# audio_spectrum.net
KiCad netlist of a schematic drawn in EAGLE
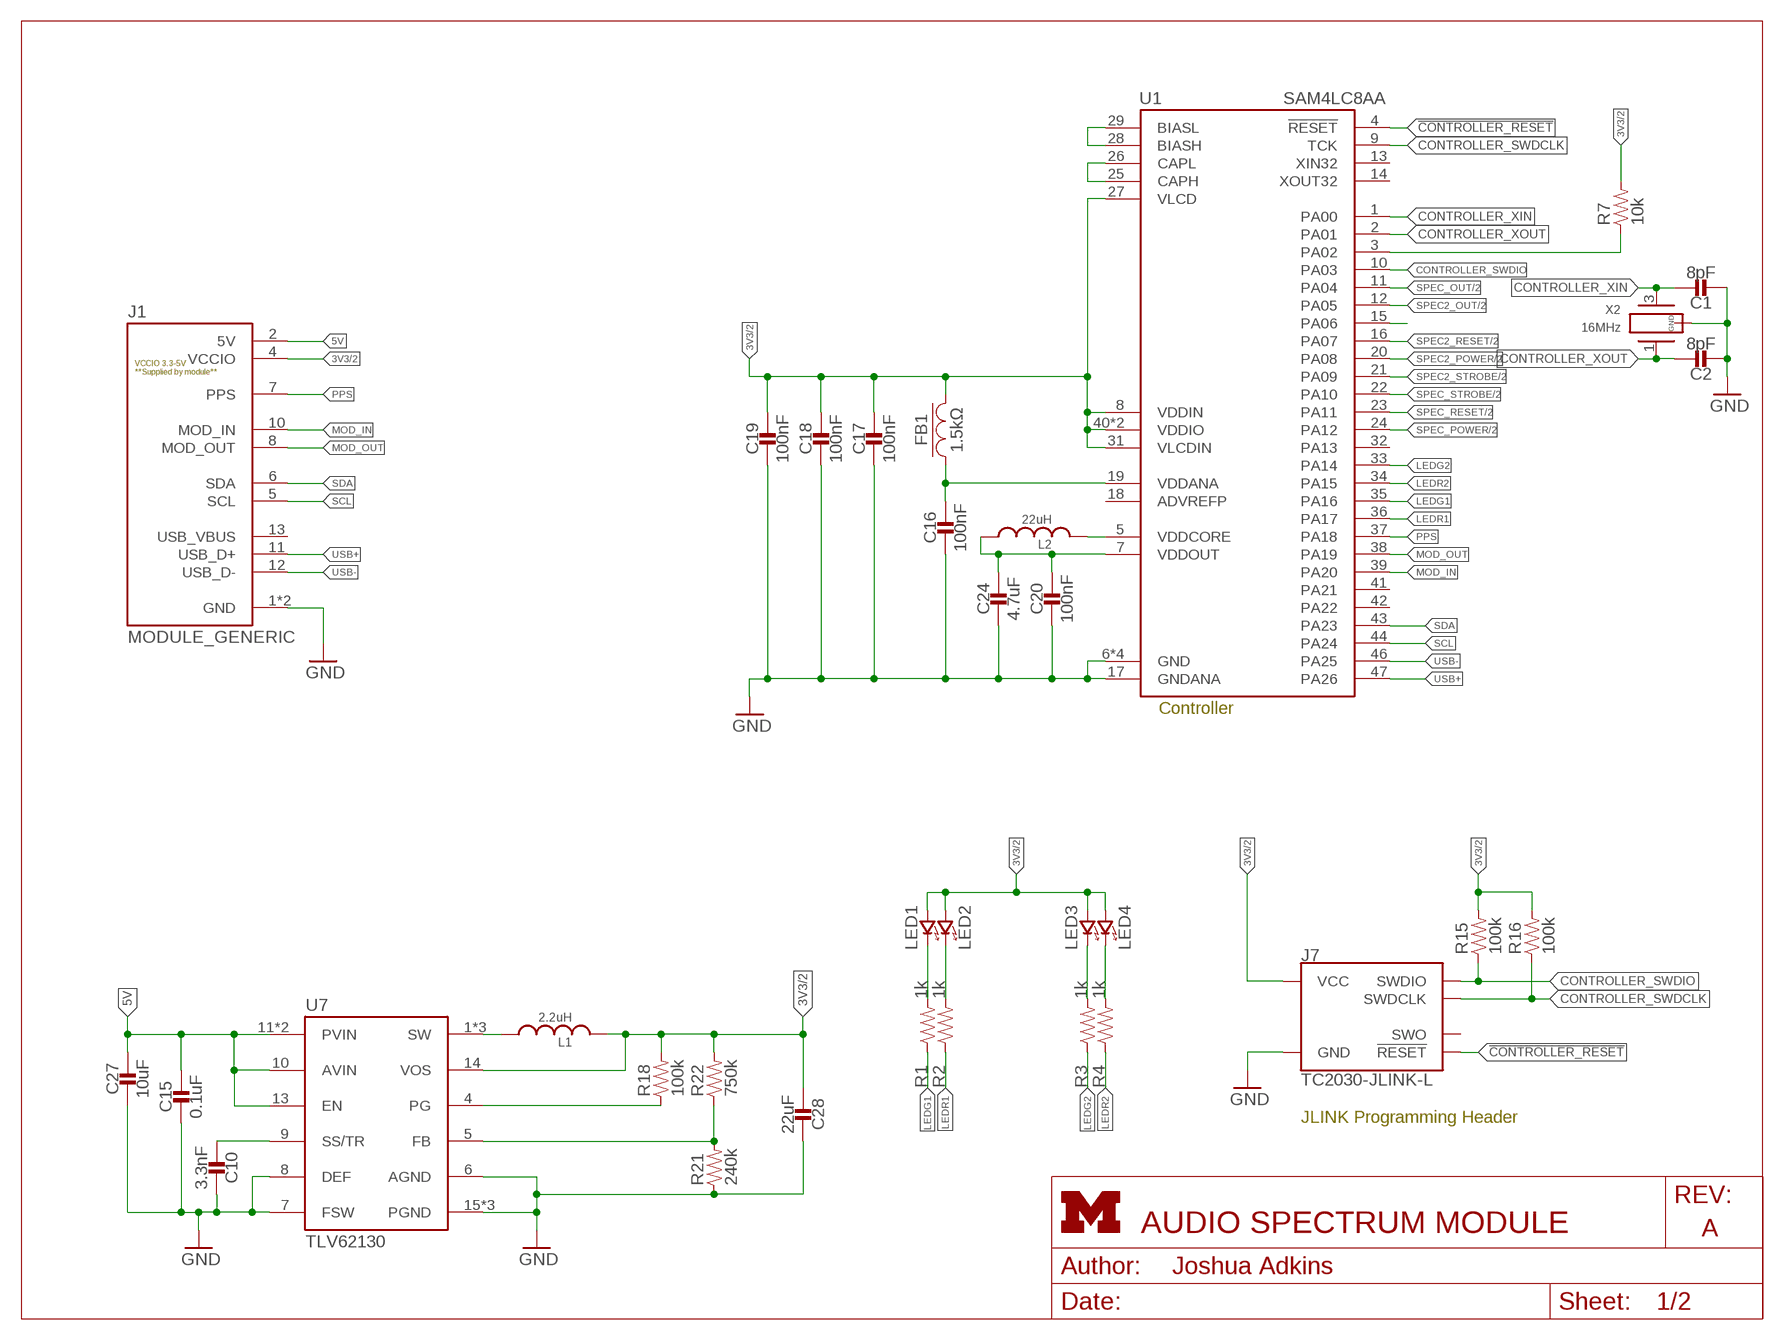
[diagram p0: schematic, sheet 1]
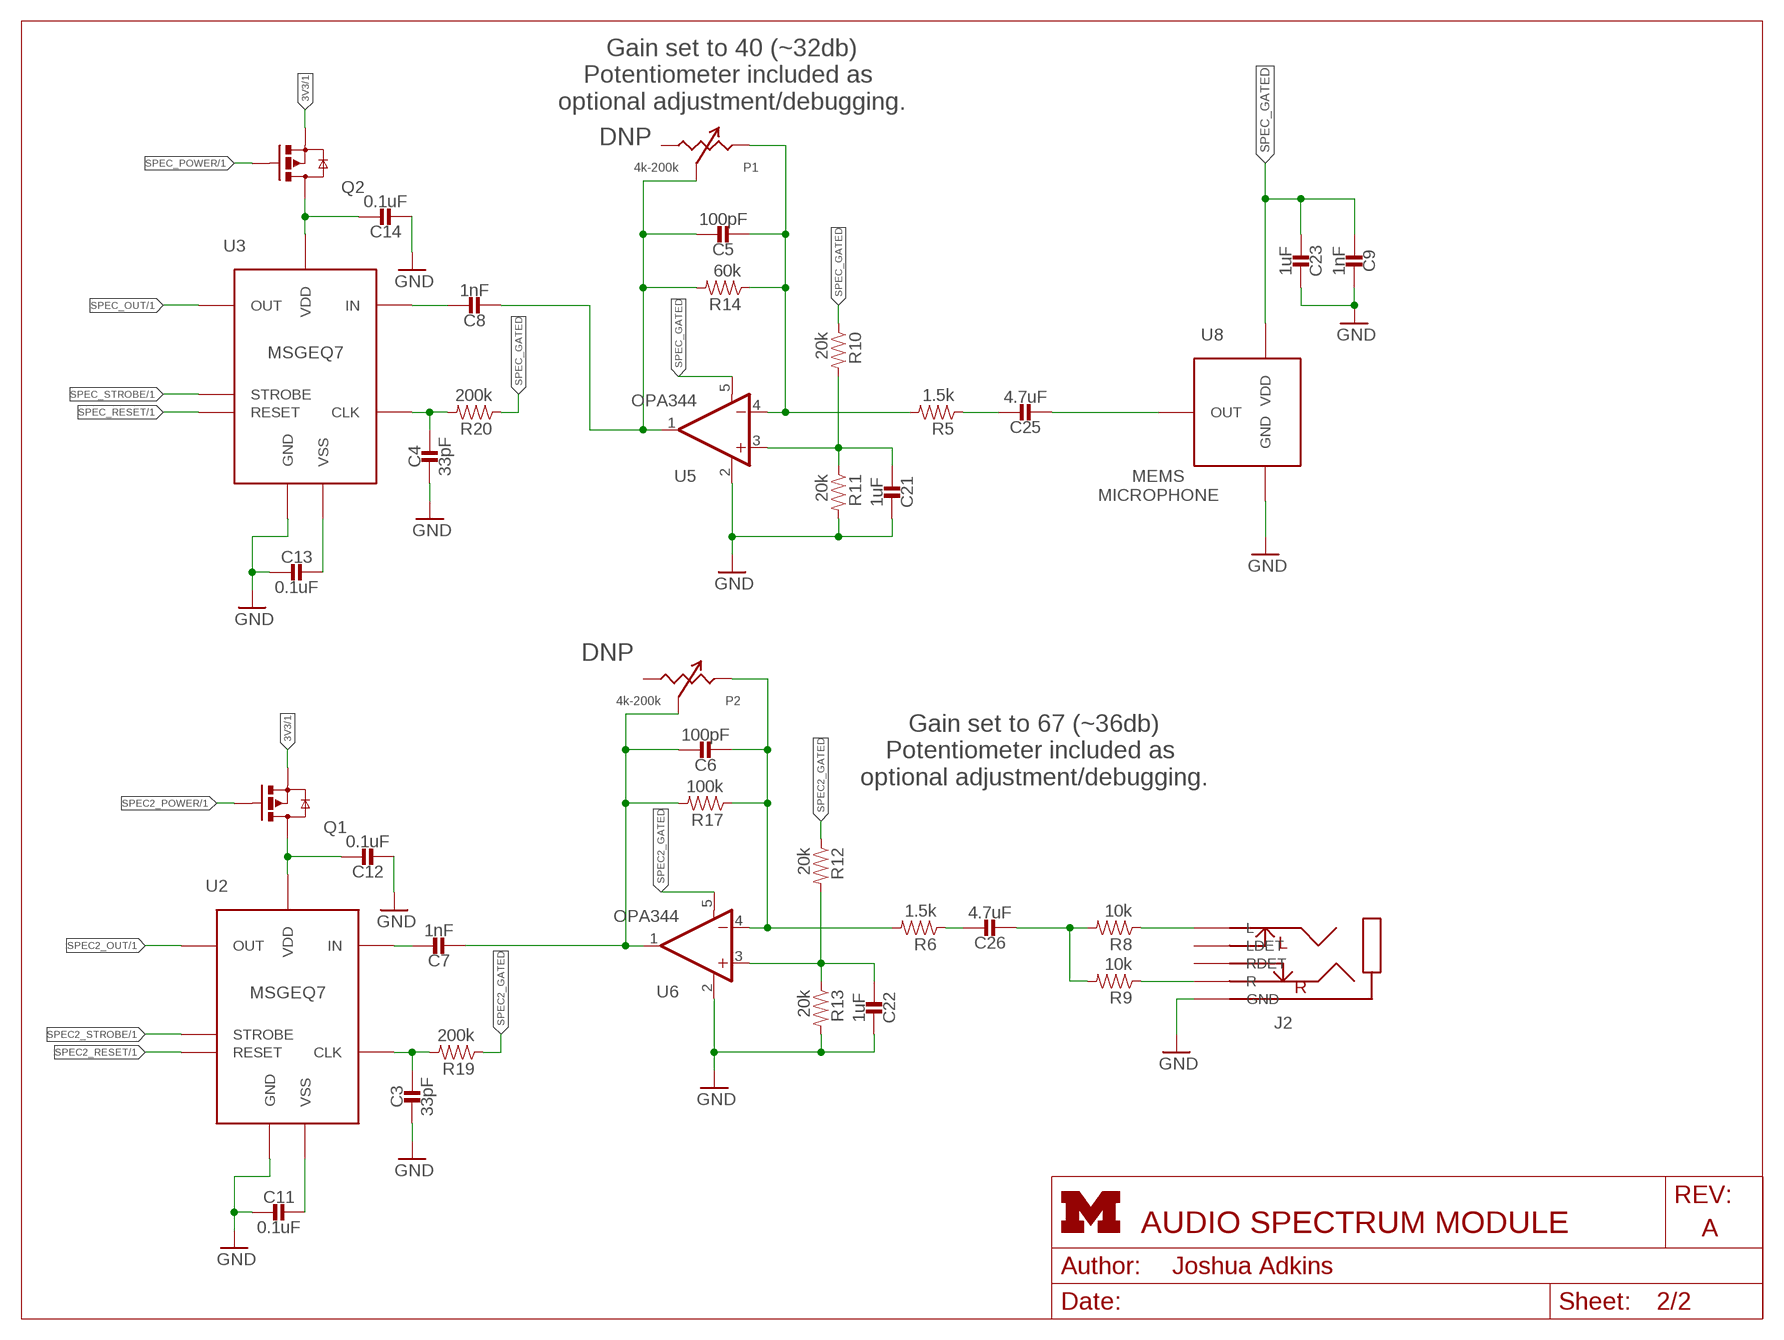
[diagram p1: schematic, sheet 2]

(export (version "E")
  (design (tool "Eeschema 10.0.6"))
  (components
    (comp (ref "C3")
      (value "33pF")
      (footprint "eagle-import:0603_CAP")
      (libsource (lib "eagle-import") (part "CAPACITOR0603_CAP"))
    )
    (comp (ref "C4")
      (value "33pF")
      (footprint "eagle-import:0603_CAP")
      (libsource (lib "eagle-import") (part "CAPACITOR0603_CAP"))
    )
    (comp (ref "C5")
      (value "100pF")
      (footprint "eagle-import:0603_CAP")
      (libsource (lib "eagle-import") (part "CAPACITOR0603_CAP"))
    )
    (comp (ref "C6")
      (value "100pF")
      (footprint "eagle-import:0603_CAP")
      (libsource (lib "eagle-import") (part "CAPACITOR0603_CAP"))
    )
    (comp (ref "C7")
      (value "1nF")
      (footprint "eagle-import:0603_CAP")
      (libsource (lib "eagle-import") (part "CAPACITOR0603_CAP"))
    )
    (comp (ref "C8")
      (value "1nF")
      (footprint "eagle-import:0603_CAP")
      (libsource (lib "eagle-import") (part "CAPACITOR0603_CAP"))
    )
    (comp (ref "C9")
      (value "1nF")
      (footprint "eagle-import:0603_CAP")
      (libsource (lib "eagle-import") (part "CAPACITOR0603_CAP"))
    )
    (comp (ref "C11")
      (value "0.1uF")
      (footprint "eagle-import:0603_CAP")
      (libsource (lib "eagle-import") (part "CAPACITOR0603_CAP"))
    )
    (comp (ref "C12")
      (value "0.1uF")
      (footprint "eagle-import:0603_CAP")
      (libsource (lib "eagle-import") (part "CAPACITOR0603_CAP"))
    )
    (comp (ref "C13")
      (value "0.1uF")
      (footprint "eagle-import:0603_CAP")
      (libsource (lib "eagle-import") (part "CAPACITOR0603_CAP"))
    )
    (comp (ref "C14")
      (value "0.1uF")
      (footprint "eagle-import:0603_CAP")
      (libsource (lib "eagle-import") (part "CAPACITOR0603_CAP"))
    )
    (comp (ref "C21")
      (value "1uF")
      (footprint "eagle-import:0603_CAP")
      (libsource (lib "eagle-import") (part "CAPACITOR0603_CAP"))
    )
    (comp (ref "C22")
      (value "1uF")
      (footprint "eagle-import:0603_CAP")
      (libsource (lib "eagle-import") (part "CAPACITOR0603_CAP"))
    )
    (comp (ref "C23")
      (value "1uF")
      (footprint "eagle-import:0603_CAP")
      (libsource (lib "eagle-import") (part "CAPACITOR0603_CAP"))
    )
    (comp (ref "C25")
      (value "4.7uF")
      (footprint "eagle-import:0603_CAP")
      (libsource (lib "eagle-import") (part "CAPACITOR0603_CAP"))
    )
    (comp (ref "C26")
      (value "4.7uF")
      (footprint "eagle-import:0603_CAP")
      (libsource (lib "eagle-import") (part "CAPACITOR0603_CAP"))
    )
    (comp (ref "J2")
      (value "AUDIO-JACK-VERTICAL")
      (footprint "eagle-import:AUDIO-JACK-VERTICAL")
      (libsource (lib "eagle-import") (part "AUDIO-JACK-VERTICAL"))
    )
    (comp (ref "P1")
      (value "4k-200k")
      (footprint "eagle-import:TC33X-2")
      (libsource (lib "eagle-import") (part "POTTC33X"))
    )
    (comp (ref "P2")
      (value "4k-200k")
      (footprint "eagle-import:TC33X-2")
      (libsource (lib "eagle-import") (part "POTTC33X"))
    )
    (comp (ref "Q1")
      (value "NX3008PBK")
      (footprint "eagle-import:SOT23-3")
      (libsource (lib "eagle-import") (part "NX3008PBK"))
    )
    (comp (ref "Q2")
      (value "NX3008PBK")
      (footprint "eagle-import:SOT23-3")
      (libsource (lib "eagle-import") (part "NX3008PBK"))
    )
    (comp (ref "R5")
      (value "1.5k")
      (footprint "eagle-import:0603-RES")
      (libsource (lib "eagle-import") (part "RESISTOR0603_RES"))
    )
    (comp (ref "R6")
      (value "1.5k")
      (footprint "eagle-import:0603-RES")
      (libsource (lib "eagle-import") (part "RESISTOR0603_RES"))
    )
    (comp (ref "R8")
      (value "10k")
      (footprint "eagle-import:0603-RES")
      (libsource (lib "eagle-import") (part "RESISTOR0603_RES"))
    )
    (comp (ref "R9")
      (value "10k")
      (footprint "eagle-import:0603-RES")
      (libsource (lib "eagle-import") (part "RESISTOR0603_RES"))
    )
    (comp (ref "R10")
      (value "20k")
      (footprint "eagle-import:0603-RES")
      (libsource (lib "eagle-import") (part "RESISTOR0603_RES"))
    )
    (comp (ref "R11")
      (value "20k")
      (footprint "eagle-import:0603-RES")
      (libsource (lib "eagle-import") (part "RESISTOR0603_RES"))
    )
    (comp (ref "R12")
      (value "20k")
      (footprint "eagle-import:0603-RES")
      (libsource (lib "eagle-import") (part "RESISTOR0603_RES"))
    )
    (comp (ref "R13")
      (value "20k")
      (footprint "eagle-import:0603-RES")
      (libsource (lib "eagle-import") (part "RESISTOR0603_RES"))
    )
    (comp (ref "R14")
      (value "60k")
      (footprint "eagle-import:0603-RES")
      (libsource (lib "eagle-import") (part "RESISTOR0603_RES"))
    )
    (comp (ref "R17")
      (value "100k")
      (footprint "eagle-import:0603-RES")
      (libsource (lib "eagle-import") (part "RESISTOR0603_RES"))
    )
    (comp (ref "R19")
      (value "200k")
      (footprint "eagle-import:0603-RES")
      (libsource (lib "eagle-import") (part "RESISTOR0603_RES"))
    )
    (comp (ref "R20")
      (value "200k")
      (footprint "eagle-import:0603-RES")
      (libsource (lib "eagle-import") (part "RESISTOR0603_RES"))
    )
    (comp (ref "U2")
      (value "MSGEQ7")
      (footprint "eagle-import:DIP-8")
      (libsource (lib "eagle-import") (part "MSGEQ7"))
    )
    (comp (ref "U3")
      (value "MSGEQ7")
      (footprint "eagle-import:DIP-8")
      (libsource (lib "eagle-import") (part "MSGEQ7"))
    )
    (comp (ref "U5")
      (value "OPA344")
      (footprint "eagle-import:SOT23-5")
      (libsource (lib "eagle-import") (part "OPA344"))
    )
    (comp (ref "U6")
      (value "OPA344")
      (footprint "eagle-import:SOT23-5")
      (libsource (lib "eagle-import") (part "OPA344"))
    )
    (comp (ref "U8")
      (value "MP23AB02B")
      (footprint "eagle-import:MP23AB02B")
      (libsource (lib "eagle-import") (part "MP23AB02B"))
    )
    (comp (ref "C1")
      (value "8pF")
      (footprint "eagle-import:0603_CAP")
      (libsource (lib "eagle-import") (part "CAPACITOR0603_CAP"))
    )
    (comp (ref "C2")
      (value "8pF")
      (footprint "eagle-import:0603_CAP")
      (libsource (lib "eagle-import") (part "CAPACITOR0603_CAP"))
    )
    (comp (ref "C10")
      (value "3.3nF")
      (footprint "eagle-import:0603_CAP")
      (libsource (lib "eagle-import") (part "CAPACITOR0603_CAP"))
    )
    (comp (ref "C15")
      (value "0.1uF")
      (footprint "eagle-import:0603_CAP")
      (libsource (lib "eagle-import") (part "CAPACITOR0603_CAP"))
    )
    (comp (ref "C16")
      (value "100nF")
      (footprint "eagle-import:0603_CAP")
      (libsource (lib "eagle-import") (part "CAPACITOR0603_CAP"))
    )
    (comp (ref "C17")
      (value "100nF")
      (footprint "eagle-import:0603_CAP")
      (libsource (lib "eagle-import") (part "CAPACITOR0603_CAP"))
    )
    (comp (ref "C18")
      (value "100nF")
      (footprint "eagle-import:0603_CAP")
      (libsource (lib "eagle-import") (part "CAPACITOR0603_CAP"))
    )
    (comp (ref "C19")
      (value "100nF")
      (footprint "eagle-import:0603_CAP")
      (libsource (lib "eagle-import") (part "CAPACITOR0603_CAP"))
    )
    (comp (ref "C20")
      (value "100nF")
      (footprint "eagle-import:0603_CAP")
      (libsource (lib "eagle-import") (part "CAPACITOR0603_CAP"))
    )
    (comp (ref "C24")
      (value "4.7uF")
      (footprint "eagle-import:0603_CAP")
      (libsource (lib "eagle-import") (part "CAPACITOR0603_CAP"))
    )
    (comp (ref "C27")
      (value "10uF")
      (footprint "eagle-import:0603_CAP")
      (libsource (lib "eagle-import") (part "CAPACITOR0603_CAP"))
    )
    (comp (ref "C28")
      (value "22uF")
      (footprint "eagle-import:0603_CAP")
      (libsource (lib "eagle-import") (part "CAPACITOR0603_CAP"))
    )
    (comp (ref "FB1")
      (value "1.5kΩ")
      (footprint "eagle-import:0603_CAP")
      (libsource (lib "eagle-import") (part "FERRITE_BEAD0603"))
    )
    (comp (ref "J1")
      (value "MODULE_GENERIC")
      (footprint "eagle-import:MODULE_GENERIC")
      (libsource (lib "eagle-import") (part "MODULE_GENERIC"))
    )
    (comp (ref "J7")
      (value "TC2030-JLINK-L")
      (footprint "eagle-import:TC2030-IDC")
      (libsource (lib "eagle-import") (part "TC2030-JLINK-L"))
    )
    (comp (ref "L1")
      (value "2.2uH")
      (footprint "eagle-import:IHL-1212BZ-11")
      (libsource (lib "eagle-import") (part "INDUCTORIHL"))
    )
    (comp (ref "L2")
      (value "22uH")
      (footprint "eagle-import:1212")
      (libsource (lib "eagle-import") (part "LHQ3NP"))
    )
    (comp (ref "LED1")
      (value "LED0603")
      (footprint "eagle-import:LED-0603")
      (libsource (lib "eagle-import") (part "LED0603"))
    )
    (comp (ref "LED2")
      (value "LED0603")
      (footprint "eagle-import:LED-0603")
      (libsource (lib "eagle-import") (part "LED0603"))
    )
    (comp (ref "LED3")
      (value "LED0603")
      (footprint "eagle-import:LED-0603")
      (libsource (lib "eagle-import") (part "LED0603"))
    )
    (comp (ref "LED4")
      (value "LED0603")
      (footprint "eagle-import:LED-0603")
      (libsource (lib "eagle-import") (part "LED0603"))
    )
    (comp (ref "R1")
      (value "1k")
      (footprint "eagle-import:0603-RES")
      (libsource (lib "eagle-import") (part "RESISTOR0603_RES"))
    )
    (comp (ref "R2")
      (value "1k")
      (footprint "eagle-import:0603-RES")
      (libsource (lib "eagle-import") (part "RESISTOR0603_RES"))
    )
    (comp (ref "R3")
      (value "1k")
      (footprint "eagle-import:0603-RES")
      (libsource (lib "eagle-import") (part "RESISTOR0603_RES"))
    )
    (comp (ref "R4")
      (value "1k")
      (footprint "eagle-import:0603-RES")
      (libsource (lib "eagle-import") (part "RESISTOR0603_RES"))
    )
    (comp (ref "R7")
      (value "10k")
      (footprint "eagle-import:0603-RES")
      (libsource (lib "eagle-import") (part "RESISTOR0603_RES"))
    )
    (comp (ref "R15")
      (value "100k")
      (footprint "eagle-import:0603-RES")
      (libsource (lib "eagle-import") (part "RESISTOR0603_RES"))
    )
    (comp (ref "R16")
      (value "100k")
      (footprint "eagle-import:0603-RES")
      (libsource (lib "eagle-import") (part "RESISTOR0603_RES"))
    )
    (comp (ref "R18")
      (value "100k")
      (footprint "eagle-import:0603-RES")
      (libsource (lib "eagle-import") (part "RESISTOR0603_RES"))
    )
    (comp (ref "R21")
      (value "240k")
      (footprint "eagle-import:0603-RES")
      (libsource (lib "eagle-import") (part "RESISTOR0603_RES"))
    )
    (comp (ref "R22")
      (value "750k")
      (footprint "eagle-import:0603-RES")
      (libsource (lib "eagle-import") (part "RESISTOR0603_RES"))
    )
    (comp (ref "U1")
      (value "SAM4LC8AA")
      (footprint "eagle-import:QFN-48-7MM")
      (libsource (lib "eagle-import") (part "SAM4LC8AA"))
    )
    (comp (ref "U7")
      (value "TLV62130")
      (footprint "eagle-import:TQFN-16_3MM")
      (libsource (lib "eagle-import") (part "TLV62130"))
    )
    (comp (ref "X2")
      (value "16MHz")
      (footprint "eagle-import:FHXXX")
      (libsource (lib "eagle-import") (part "FH1600015"))
    )
  )
  (nets
    (net (code "1") (name "3V3") (class "Default")
      (node (ref "C17") (pin "1") (pinfunction "1_1") (pintype "bidirectional"))
      (node (ref "C18") (pin "1") (pinfunction "1_1") (pintype "bidirectional"))
      (node (ref "C19") (pin "1") (pinfunction "1_1") (pintype "bidirectional"))
      (node (ref "C28") (pin "2") (pinfunction "2_2") (pintype "bidirectional"))
      (node (ref "FB1") (pin "2") (pinfunction "P$2_2") (pintype "bidirectional"))
      (node (ref "J1") (pin "4") (pinfunction "VCCIO_4") (pintype "bidirectional"))
      (node (ref "J7") (pin "1") (pinfunction "VCC_1") (pintype "bidirectional"))
      (node (ref "L1") (pin "P$2") (pinfunction "2_P$2") (pintype "bidirectional"))
      (node (ref "LED1") (pin "A") (pinfunction "ANODE_A") (pintype "bidirectional"))
      (node (ref "LED2") (pin "A") (pinfunction "ANODE_A") (pintype "bidirectional"))
      (node (ref "LED3") (pin "A") (pinfunction "ANODE_A") (pintype "bidirectional"))
      (node (ref "LED4") (pin "A") (pinfunction "ANODE_A") (pintype "bidirectional"))
      (node (ref "Q1") (pin "2") (pinfunction "S_2") (pintype "passive"))
      (node (ref "Q2") (pin "2") (pinfunction "S_2") (pintype "passive"))
      (node (ref "R15") (pin "2") (pinfunction "2_2") (pintype "passive"))
      (node (ref "R16") (pin "2") (pinfunction "2_2") (pintype "passive"))
      (node (ref "R18") (pin "2") (pinfunction "2_2") (pintype "passive"))
      (node (ref "R22") (pin "2") (pinfunction "2_2") (pintype "passive"))
      (node (ref "R7") (pin "2") (pinfunction "2_2") (pintype "passive"))
      (node (ref "U1") (pin "27") (pinfunction "VLCD_27") (pintype "bidirectional"))
      (node (ref "U1") (pin "31") (pinfunction "VLCDIN_31") (pintype "power_in"))
      (node (ref "U1") (pin "40") (pinfunction "VDDIO_40") (pintype "power_in"))
      (node (ref "U1") (pin "45") (pinfunction "VDDIO_45") (pintype "power_in"))
      (node (ref "U1") (pin "8") (pinfunction "VDDIN_8") (pintype "power_in"))
      (node (ref "U7") (pin "14") (pinfunction "VOS_14") (pintype "bidirectional"))
    )
    (net (code "2") (name "5V") (class "Default")
      (node (ref "C15") (pin "1") (pinfunction "1_1") (pintype "bidirectional"))
      (node (ref "C27") (pin "1") (pinfunction "1_1") (pintype "bidirectional"))
      (node (ref "J1") (pin "2") (pinfunction "5V_2") (pintype "bidirectional"))
      (node (ref "U7") (pin "10") (pinfunction "AVIN_10") (pintype "bidirectional"))
      (node (ref "U7") (pin "11") (pinfunction "PVIN_11") (pintype "bidirectional"))
      (node (ref "U7") (pin "12") (pinfunction "PVIN_12") (pintype "bidirectional"))
      (node (ref "U7") (pin "13") (pinfunction "EN_13") (pintype "bidirectional"))
    )
    (net (code "3") (name "CONTROLLER_SWDCLK") (class "Default")
      (node (ref "J7") (pin "4") (pinfunction "SWDCLK_4") (pintype "bidirectional"))
      (node (ref "R16") (pin "1") (pinfunction "1_1") (pintype "passive"))
      (node (ref "U1") (pin "9") (pinfunction "TCK_9") (pintype "bidirectional"))
    )
    (net (code "4") (name "CONTROLLER_SWDIO") (class "Default")
      (node (ref "J7") (pin "2") (pinfunction "SWDIO_2") (pintype "bidirectional"))
      (node (ref "R15") (pin "1") (pinfunction "1_1") (pintype "passive"))
      (node (ref "U1") (pin "10") (pinfunction "PA03_10") (pintype "bidirectional"))
    )
    (net (code "5") (name "CONTROLLER_XIN") (class "Default")
      (node (ref "C1") (pin "1") (pinfunction "1_1") (pintype "bidirectional"))
      (node (ref "U1") (pin "1") (pinfunction "PA00_1") (pintype "bidirectional"))
      (node (ref "X2") (pin "3") (pinfunction "2_3") (pintype "bidirectional"))
    )
    (net (code "6") (name "CONTROLLER_XOUT") (class "Default")
      (node (ref "C2") (pin "1") (pinfunction "1_1") (pintype "bidirectional"))
      (node (ref "U1") (pin "2") (pinfunction "PA01_2") (pintype "bidirectional"))
      (node (ref "X2") (pin "1") (pinfunction "1_1") (pintype "bidirectional"))
    )
    (net (code "7") (name "GND") (class "Default")
      (node (ref "C1") (pin "2") (pinfunction "2_2") (pintype "bidirectional"))
      (node (ref "C10") (pin "1") (pinfunction "1_1") (pintype "bidirectional"))
      (node (ref "C11") (pin "2") (pinfunction "2_2") (pintype "bidirectional"))
      (node (ref "C12") (pin "2") (pinfunction "2_2") (pintype "bidirectional"))
      (node (ref "C13") (pin "2") (pinfunction "2_2") (pintype "bidirectional"))
      (node (ref "C14") (pin "2") (pinfunction "2_2") (pintype "bidirectional"))
      (node (ref "C15") (pin "2") (pinfunction "2_2") (pintype "bidirectional"))
      (node (ref "C16") (pin "2") (pinfunction "2_2") (pintype "bidirectional"))
      (node (ref "C17") (pin "2") (pinfunction "2_2") (pintype "bidirectional"))
      (node (ref "C18") (pin "2") (pinfunction "2_2") (pintype "bidirectional"))
      (node (ref "C19") (pin "2") (pinfunction "2_2") (pintype "bidirectional"))
      (node (ref "C2") (pin "2") (pinfunction "2_2") (pintype "bidirectional"))
      (node (ref "C20") (pin "2") (pinfunction "2_2") (pintype "bidirectional"))
      (node (ref "C21") (pin "1") (pinfunction "1_1") (pintype "bidirectional"))
      (node (ref "C22") (pin "1") (pinfunction "1_1") (pintype "bidirectional"))
      (node (ref "C23") (pin "1") (pinfunction "1_1") (pintype "bidirectional"))
      (node (ref "C24") (pin "2") (pinfunction "2_2") (pintype "bidirectional"))
      (node (ref "C27") (pin "2") (pinfunction "2_2") (pintype "bidirectional"))
      (node (ref "C28") (pin "1") (pinfunction "1_1") (pintype "bidirectional"))
      (node (ref "C3") (pin "2") (pinfunction "2_2") (pintype "bidirectional"))
      (node (ref "C4") (pin "2") (pinfunction "2_2") (pintype "bidirectional"))
      (node (ref "C9") (pin "1") (pinfunction "1_1") (pintype "bidirectional"))
      (node (ref "J1") (pin "1") (pinfunction "GND_1") (pintype "bidirectional"))
      (node (ref "J1") (pin "14") (pinfunction "GND_14") (pintype "bidirectional"))
      (node (ref "J2") (pin "5") (pinfunction "GND_5") (pintype "bidirectional"))
      (node (ref "J7") (pin "5") (pinfunction "GND_5") (pintype "bidirectional"))
      (node (ref "R11") (pin "2") (pinfunction "2_2") (pintype "passive"))
      (node (ref "R13") (pin "2") (pinfunction "2_2") (pintype "passive"))
      (node (ref "R21") (pin "1") (pinfunction "1_1") (pintype "passive"))
      (node (ref "U1") (pin "17") (pinfunction "GNDANA_17") (pintype "power_in"))
      (node (ref "U1") (pin "30") (pinfunction "GND_30") (pintype "power_in"))
      (node (ref "U1") (pin "48") (pinfunction "GND_48") (pintype "power_in"))
      (node (ref "U1") (pin "6") (pinfunction "GND_6") (pintype "power_in"))
      (node (ref "U1") (pin "THERMAL") (pinfunction "GND_THERMAL") (pintype "power_in"))
      (node (ref "U2") (pin "6") (pinfunction "GND_6") (pintype "bidirectional"))
      (node (ref "U3") (pin "6") (pinfunction "GND_6") (pintype "bidirectional"))
      (node (ref "U5") (pin "2") (pinfunction "V-_2") (pintype "power_in"))
      (node (ref "U6") (pin "2") (pinfunction "V-_2") (pintype "power_in"))
      (node (ref "U7") (pin "15") (pinfunction "PGND_15") (pintype "bidirectional"))
      (node (ref "U7") (pin "16") (pinfunction "PGND_16") (pintype "bidirectional"))
      (node (ref "U7") (pin "6") (pinfunction "AGND_6") (pintype "bidirectional"))
      (node (ref "U7") (pin "7") (pinfunction "FSW_7") (pintype "bidirectional"))
      (node (ref "U7") (pin "8") (pinfunction "DEF_8") (pintype "bidirectional"))
      (node (ref "U7") (pin "GND") (pinfunction "PGND_GND") (pintype "bidirectional"))
      (node (ref "U8") (pin "3") (pinfunction "GND_3") (pintype "bidirectional"))
      (node (ref "X2") (pin "2") (pinfunction "GND_2") (pintype "bidirectional"))
      (node (ref "X2") (pin "4") (pinfunction "GND_4") (pintype "bidirectional"))
    )
    (net (code "8") (name "LEDG1") (class "Default")
      (node (ref "R1") (pin "1") (pinfunction "1_1") (pintype "passive"))
      (node (ref "U1") (pin "35") (pinfunction "PA16_35") (pintype "bidirectional"))
    )
    (net (code "9") (name "LEDG2") (class "Default")
      (node (ref "R3") (pin "1") (pinfunction "1_1") (pintype "passive"))
      (node (ref "U1") (pin "33") (pinfunction "PA14_33") (pintype "bidirectional"))
    )
    (net (code "10") (name "LEDR1") (class "Default")
      (node (ref "R2") (pin "1") (pinfunction "1_1") (pintype "passive"))
      (node (ref "U1") (pin "36") (pinfunction "PA17_36") (pintype "bidirectional"))
    )
    (net (code "11") (name "LEDR2") (class "Default")
      (node (ref "R4") (pin "1") (pinfunction "1_1") (pintype "passive"))
      (node (ref "U1") (pin "34") (pinfunction "PA15_34") (pintype "bidirectional"))
    )
    (net (code "12") (name "MOD_IN") (class "Default")
      (node (ref "J1") (pin "10") (pinfunction "MOD_IN_10") (pintype "bidirectional"))
      (node (ref "U1") (pin "39") (pinfunction "PA20_39") (pintype "bidirectional"))
    )
    (net (code "13") (name "MOD_OUT") (class "Default")
      (node (ref "J1") (pin "8") (pinfunction "MOD_OUT_8") (pintype "bidirectional"))
      (node (ref "U1") (pin "38") (pinfunction "PA19_38") (pintype "bidirectional"))
    )
    (net (code "14") (name "Net-(C25-Pad1)") (class "Default")
      (node (ref "C25") (pin "1") (pinfunction "1_1") (pintype "bidirectional"))
      (node (ref "R5") (pin "1") (pinfunction "1_1") (pintype "passive"))
    )
    (net (code "15") (name "Net-(C26-Pad1)") (class "Default")
      (node (ref "C26") (pin "1") (pinfunction "1_1") (pintype "bidirectional"))
      (node (ref "R6") (pin "1") (pinfunction "1_1") (pintype "passive"))
    )
    (net (code "16") (name "Net-(C26-Pad2)") (class "Default")
      (node (ref "C26") (pin "2") (pinfunction "2_2") (pintype "bidirectional"))
      (node (ref "R8") (pin "2") (pinfunction "2_2") (pintype "passive"))
      (node (ref "R9") (pin "2") (pinfunction "2_2") (pintype "passive"))
    )
    (net (code "17") (name "Net-(FB1-P$1)") (class "Default")
      (node (ref "C16") (pin "1") (pinfunction "1_1") (pintype "bidirectional"))
      (node (ref "FB1") (pin "1") (pinfunction "P$1_1") (pintype "bidirectional"))
      (node (ref "U1") (pin "19") (pinfunction "VDDANA_19") (pintype "power_in"))
    )
    (net (code "18") (name "Net-(J2-L)") (class "Default")
      (node (ref "J2") (pin "4") (pinfunction "L_4") (pintype "bidirectional"))
      (node (ref "R8") (pin "1") (pinfunction "1_1") (pintype "passive"))
    )
    (net (code "19") (name "Net-(J2-R)") (class "Default")
      (node (ref "J2") (pin "1") (pinfunction "R_1") (pintype "bidirectional"))
      (node (ref "R9") (pin "1") (pinfunction "1_1") (pintype "passive"))
    )
    (net (code "20") (name "Net-(L1-1)") (class "Default")
      (node (ref "L1") (pin "P$1") (pinfunction "1_P$1") (pintype "bidirectional"))
      (node (ref "U7") (pin "1") (pinfunction "SW_1") (pintype "bidirectional"))
      (node (ref "U7") (pin "2") (pinfunction "SW_2") (pintype "bidirectional"))
      (node (ref "U7") (pin "3") (pinfunction "SW_3") (pintype "bidirectional"))
    )
    (net (code "21") (name "Net-(L2-1)") (class "Default")
      (node (ref "C20") (pin "1") (pinfunction "1_1") (pintype "bidirectional"))
      (node (ref "C24") (pin "1") (pinfunction "1_1") (pintype "bidirectional"))
      (node (ref "L2") (pin "P$1") (pinfunction "1_P$1") (pintype "bidirectional"))
      (node (ref "U1") (pin "7") (pinfunction "VDDOUT_7") (pintype "power_in"))
    )
    (net (code "22") (name "Net-(L2-2)") (class "Default")
      (node (ref "L2") (pin "P$2") (pinfunction "2_P$2") (pintype "bidirectional"))
      (node (ref "U1") (pin "5") (pinfunction "VDDCORE_5") (pintype "power_in"))
    )
    (net (code "23") (name "Net-(LED1-CATHODE)") (class "Default")
      (node (ref "LED1") (pin "C") (pinfunction "CATHODE_C") (pintype "bidirectional"))
      (node (ref "R1") (pin "2") (pinfunction "2_2") (pintype "passive"))
    )
    (net (code "24") (name "Net-(LED2-CATHODE)") (class "Default")
      (node (ref "LED2") (pin "C") (pinfunction "CATHODE_C") (pintype "bidirectional"))
      (node (ref "R2") (pin "2") (pinfunction "2_2") (pintype "passive"))
    )
    (net (code "25") (name "Net-(LED3-CATHODE)") (class "Default")
      (node (ref "LED3") (pin "C") (pinfunction "CATHODE_C") (pintype "bidirectional"))
      (node (ref "R3") (pin "2") (pinfunction "2_2") (pintype "passive"))
    )
    (net (code "26") (name "Net-(LED4-CATHODE)") (class "Default")
      (node (ref "LED4") (pin "C") (pinfunction "CATHODE_C") (pintype "bidirectional"))
      (node (ref "R4") (pin "2") (pinfunction "2_2") (pintype "passive"))
    )
    (net (code "27") (name "Net-(P1-CW)") (class "Default")
      (node (ref "C5") (pin "2") (pinfunction "2_2") (pintype "bidirectional"))
      (node (ref "P1") (pin "2") (pinfunction "CW_2") (pintype "bidirectional"))
      (node (ref "R14") (pin "1") (pinfunction "1_1") (pintype "passive"))
      (node (ref "R5") (pin "2") (pinfunction "2_2") (pintype "passive"))
      (node (ref "U5") (pin "4") (pinfunction "-IN_4") (pintype "input"))
    )
    (net (code "28") (name "Net-(P1-W)") (class "Default")
      (node (ref "C5") (pin "1") (pinfunction "1_1") (pintype "bidirectional"))
      (node (ref "C8") (pin "2") (pinfunction "2_2") (pintype "bidirectional"))
      (node (ref "P1") (pin "3") (pinfunction "W_3") (pintype "bidirectional"))
      (node (ref "R14") (pin "2") (pinfunction "2_2") (pintype "passive"))
      (node (ref "U5") (pin "1") (pinfunction "OUT_1") (pintype "output"))
    )
    (net (code "29") (name "Net-(P2-CW)") (class "Default")
      (node (ref "C6") (pin "2") (pinfunction "2_2") (pintype "bidirectional"))
      (node (ref "P2") (pin "2") (pinfunction "CW_2") (pintype "bidirectional"))
      (node (ref "R17") (pin "1") (pinfunction "1_1") (pintype "passive"))
      (node (ref "R6") (pin "2") (pinfunction "2_2") (pintype "passive"))
      (node (ref "U6") (pin "4") (pinfunction "-IN_4") (pintype "input"))
    )
    (net (code "30") (name "Net-(P2-W)") (class "Default")
      (node (ref "C6") (pin "1") (pinfunction "1_1") (pintype "bidirectional"))
      (node (ref "C7") (pin "2") (pinfunction "2_2") (pintype "bidirectional"))
      (node (ref "P2") (pin "3") (pinfunction "W_3") (pintype "bidirectional"))
      (node (ref "R17") (pin "2") (pinfunction "2_2") (pintype "passive"))
      (node (ref "U6") (pin "1") (pinfunction "OUT_1") (pintype "output"))
    )
    (net (code "31") (name "Net-(U1-BIASH)") (class "Default")
      (node (ref "U1") (pin "28") (pinfunction "BIASH_28") (pintype "bidirectional"))
      (node (ref "U1") (pin "29") (pinfunction "BIASL_29") (pintype "bidirectional"))
    )
    (net (code "32") (name "Net-(U1-CAPH)") (class "Default")
      (node (ref "U1") (pin "25") (pinfunction "CAPH_25") (pintype "bidirectional"))
      (node (ref "U1") (pin "26") (pinfunction "CAPL_26") (pintype "bidirectional"))
    )
    (net (code "33") (name "Net-(U1-PA02)") (class "Default")
      (node (ref "R7") (pin "1") (pinfunction "1_1") (pintype "passive"))
      (node (ref "U1") (pin "3") (pinfunction "PA02_3") (pintype "bidirectional"))
    )
    (net (code "34") (name "Net-(U2-CLK)") (class "Default")
      (node (ref "C3") (pin "1") (pinfunction "1_1") (pintype "bidirectional"))
      (node (ref "R19") (pin "2") (pinfunction "2_2") (pintype "passive"))
      (node (ref "U2") (pin "8") (pinfunction "CLK_8") (pintype "bidirectional"))
    )
    (net (code "35") (name "Net-(U2-IN)") (class "Default")
      (node (ref "C7") (pin "1") (pinfunction "1_1") (pintype "bidirectional"))
      (node (ref "U2") (pin "5") (pinfunction "IN_5") (pintype "bidirectional"))
    )
    (net (code "36") (name "Net-(U2-VSS)") (class "Default")
      (node (ref "C11") (pin "1") (pinfunction "1_1") (pintype "bidirectional"))
      (node (ref "U2") (pin "2") (pinfunction "VSS_2") (pintype "bidirectional"))
    )
    (net (code "37") (name "Net-(U3-CLK)") (class "Default")
      (node (ref "C4") (pin "1") (pinfunction "1_1") (pintype "bidirectional"))
      (node (ref "R20") (pin "2") (pinfunction "2_2") (pintype "passive"))
      (node (ref "U3") (pin "8") (pinfunction "CLK_8") (pintype "bidirectional"))
    )
    (net (code "38") (name "Net-(U3-IN)") (class "Default")
      (node (ref "C8") (pin "1") (pinfunction "1_1") (pintype "bidirectional"))
      (node (ref "U3") (pin "5") (pinfunction "IN_5") (pintype "bidirectional"))
    )
    (net (code "39") (name "Net-(U3-VSS)") (class "Default")
      (node (ref "C13") (pin "1") (pinfunction "1_1") (pintype "bidirectional"))
      (node (ref "U3") (pin "2") (pinfunction "VSS_2") (pintype "bidirectional"))
    )
    (net (code "40") (name "Net-(U5-+IN)") (class "Default")
      (node (ref "C21") (pin "2") (pinfunction "2_2") (pintype "bidirectional"))
      (node (ref "R10") (pin "2") (pinfunction "2_2") (pintype "passive"))
      (node (ref "R11") (pin "1") (pinfunction "1_1") (pintype "passive"))
      (node (ref "U5") (pin "3") (pinfunction "+IN_3") (pintype "input"))
    )
    (net (code "41") (name "Net-(U6-+IN)") (class "Default")
      (node (ref "C22") (pin "2") (pinfunction "2_2") (pintype "bidirectional"))
      (node (ref "R12") (pin "2") (pinfunction "2_2") (pintype "passive"))
      (node (ref "R13") (pin "1") (pinfunction "1_1") (pintype "passive"))
      (node (ref "U6") (pin "3") (pinfunction "+IN_3") (pintype "input"))
    )
    (net (code "42") (name "Net-(U7-FB)") (class "Default")
      (node (ref "R21") (pin "2") (pinfunction "2_2") (pintype "passive"))
      (node (ref "R22") (pin "1") (pinfunction "1_1") (pintype "passive"))
      (node (ref "U7") (pin "5") (pinfunction "FB_5") (pintype "bidirectional"))
    )
    (net (code "43") (name "Net-(U7-PG)") (class "Default")
      (node (ref "R18") (pin "1") (pinfunction "1_1") (pintype "passive"))
      (node (ref "U7") (pin "4") (pinfunction "PG_4") (pintype "bidirectional"))
    )
    (net (code "44") (name "Net-(U7-SS{slash}TR)") (class "Default")
      (node (ref "C10") (pin "2") (pinfunction "2_2") (pintype "bidirectional"))
      (node (ref "U7") (pin "9") (pinfunction "SS/TR_9") (pintype "bidirectional"))
    )
    (net (code "45") (name "Net-(U8-OUT)") (class "Default")
      (node (ref "C25") (pin "2") (pinfunction "2_2") (pintype "bidirectional"))
      (node (ref "U8") (pin "1") (pinfunction "OUT_1") (pintype "bidirectional"))
    )
    (net (code "46") (name "PPS") (class "Default")
      (node (ref "J1") (pin "7") (pinfunction "PPS_7") (pintype "bidirectional"))
      (node (ref "U1") (pin "37") (pinfunction "PA18_37") (pintype "bidirectional"))
    )
    (net (code "47") (name "SCL") (class "Default")
      (node (ref "J1") (pin "5") (pinfunction "SCL_5") (pintype "bidirectional"))
      (node (ref "U1") (pin "44") (pinfunction "PA24_44") (pintype "bidirectional"))
    )
    (net (code "48") (name "SDA") (class "Default")
      (node (ref "J1") (pin "6") (pinfunction "SDA_6") (pintype "bidirectional"))
      (node (ref "U1") (pin "43") (pinfunction "PA23_43") (pintype "bidirectional"))
    )
    (net (code "49") (name "SPEC2_GATED") (class "Default")
      (node (ref "C12") (pin "1") (pinfunction "1_1") (pintype "bidirectional"))
      (node (ref "Q1") (pin "3") (pinfunction "D_3") (pintype "passive"))
      (node (ref "R12") (pin "1") (pinfunction "1_1") (pintype "passive"))
      (node (ref "R19") (pin "1") (pinfunction "1_1") (pintype "passive"))
      (node (ref "U2") (pin "1") (pinfunction "VDD_1") (pintype "bidirectional"))
      (node (ref "U6") (pin "5") (pinfunction "V+_5") (pintype "power_in"))
    )
    (net (code "50") (name "SPEC2_OUT") (class "Default")
      (node (ref "U1") (pin "12") (pinfunction "PA05_12") (pintype "bidirectional"))
      (node (ref "U2") (pin "3") (pinfunction "OUT_3") (pintype "bidirectional"))
    )
    (net (code "51") (name "SPEC2_POWER") (class "Default")
      (node (ref "Q1") (pin "1") (pinfunction "G_1") (pintype "passive"))
      (node (ref "U1") (pin "20") (pinfunction "PA08_20") (pintype "bidirectional"))
    )
    (net (code "52") (name "SPEC2_RESET") (class "Default")
      (node (ref "U1") (pin "16") (pinfunction "PA07_16") (pintype "bidirectional"))
      (node (ref "U2") (pin "7") (pinfunction "RESET_7") (pintype "bidirectional"))
    )
    (net (code "53") (name "SPEC2_STROBE") (class "Default")
      (node (ref "U1") (pin "21") (pinfunction "PA09_21") (pintype "bidirectional"))
      (node (ref "U2") (pin "4") (pinfunction "STROBE_4") (pintype "bidirectional"))
    )
    (net (code "54") (name "SPEC_GATED") (class "Default")
      (node (ref "C14") (pin "1") (pinfunction "1_1") (pintype "bidirectional"))
      (node (ref "C23") (pin "2") (pinfunction "2_2") (pintype "bidirectional"))
      (node (ref "C9") (pin "2") (pinfunction "2_2") (pintype "bidirectional"))
      (node (ref "Q2") (pin "3") (pinfunction "D_3") (pintype "passive"))
      (node (ref "R10") (pin "1") (pinfunction "1_1") (pintype "passive"))
      (node (ref "R20") (pin "1") (pinfunction "1_1") (pintype "passive"))
      (node (ref "U3") (pin "1") (pinfunction "VDD_1") (pintype "bidirectional"))
      (node (ref "U5") (pin "5") (pinfunction "V+_5") (pintype "power_in"))
      (node (ref "U8") (pin "2") (pinfunction "VDD_2") (pintype "bidirectional"))
    )
    (net (code "55") (name "SPEC_OUT") (class "Default")
      (node (ref "U1") (pin "11") (pinfunction "PA04_11") (pintype "bidirectional"))
      (node (ref "U3") (pin "3") (pinfunction "OUT_3") (pintype "bidirectional"))
    )
    (net (code "56") (name "SPEC_POWER") (class "Default")
      (node (ref "Q2") (pin "1") (pinfunction "G_1") (pintype "passive"))
      (node (ref "U1") (pin "24") (pinfunction "PA12_24") (pintype "bidirectional"))
    )
    (net (code "57") (name "SPEC_RESET") (class "Default")
      (node (ref "U1") (pin "23") (pinfunction "PA11_23") (pintype "bidirectional"))
      (node (ref "U3") (pin "7") (pinfunction "RESET_7") (pintype "bidirectional"))
    )
    (net (code "58") (name "SPEC_STROBE") (class "Default")
      (node (ref "U1") (pin "22") (pinfunction "PA10_22") (pintype "bidirectional"))
      (node (ref "U3") (pin "4") (pinfunction "STROBE_4") (pintype "bidirectional"))
    )
    (net (code "59") (name "USB+") (class "Default")
      (node (ref "J1") (pin "11") (pinfunction "USB_D+_11") (pintype "bidirectional"))
      (node (ref "U1") (pin "47") (pinfunction "PA26_47") (pintype "bidirectional"))
    )
    (net (code "60") (name "USB-") (class "Default")
      (node (ref "J1") (pin "12") (pinfunction "USB_D-_12") (pintype "bidirectional"))
      (node (ref "U1") (pin "46") (pinfunction "PA25_46") (pintype "bidirectional"))
    )
    (net (code "61") (name "unconnected-(J1-USB_VBUS-Pad13)") (class "Default")
      (node (ref "J1") (pin "13") (pinfunction "USB_VBUS_13") (pintype "bidirectional"))
    )
    (net (code "62") (name "unconnected-(J2-LDET-Pad3)") (class "Default")
      (node (ref "J2") (pin "3") (pinfunction "LDET_3") (pintype "bidirectional"))
    )
    (net (code "63") (name "unconnected-(J2-RDET-Pad2)") (class "Default")
      (node (ref "J2") (pin "2") (pinfunction "RDET_2") (pintype "bidirectional"))
    )
    (net (code "64") (name "unconnected-(J7-SWO-Pad6)") (class "Default")
      (node (ref "J7") (pin "6") (pinfunction "SWO_6") (pintype "bidirectional"))
    )
    (net (code "65") (name "unconnected-(P1-CCW-Pad1)") (class "Default")
      (node (ref "P1") (pin "1") (pinfunction "CCW_1") (pintype "bidirectional"))
    )
    (net (code "66") (name "unconnected-(P2-CCW-Pad1)") (class "Default")
      (node (ref "P2") (pin "1") (pinfunction "CCW_1") (pintype "bidirectional"))
    )
    (net (code "67") (name "unconnected-(U1-ADVREFP-Pad18)") (class "Default")
      (node (ref "U1") (pin "18") (pinfunction "ADVREFP_18") (pintype "bidirectional"))
    )
    (net (code "68") (name "unconnected-(U1-PA06-Pad15)") (class "Default")
      (node (ref "U1") (pin "15") (pinfunction "PA06_15") (pintype "bidirectional"))
    )
    (net (code "69") (name "unconnected-(U1-PA13-Pad32)") (class "Default")
      (node (ref "U1") (pin "32") (pinfunction "PA13_32") (pintype "bidirectional"))
    )
    (net (code "70") (name "unconnected-(U1-PA21-Pad41)") (class "Default")
      (node (ref "U1") (pin "41") (pinfunction "PA21_41") (pintype "bidirectional"))
    )
    (net (code "71") (name "unconnected-(U1-PA22-Pad42)") (class "Default")
      (node (ref "U1") (pin "42") (pinfunction "PA22_42") (pintype "bidirectional"))
    )
    (net (code "72") (name "unconnected-(U1-XIN32-Pad13)") (class "Default")
      (node (ref "U1") (pin "13") (pinfunction "XIN32_13") (pintype "bidirectional"))
    )
    (net (code "73") (name "unconnected-(U1-XOUT32-Pad14)") (class "Default")
      (node (ref "U1") (pin "14") (pinfunction "XOUT32_14") (pintype "bidirectional"))
    )
    (net (code "74") (name "~{CONTROLLER_RESET}") (class "Default")
      (node (ref "J7") (pin "3") (pinfunction "~{RESET}_3") (pintype "bidirectional"))
      (node (ref "U1") (pin "4") (pinfunction "~{RESET}_4") (pintype "bidirectional"))
    )
  )
)
